# DACs.net
KiCad netlist of a schematic drawn in Altium Designer
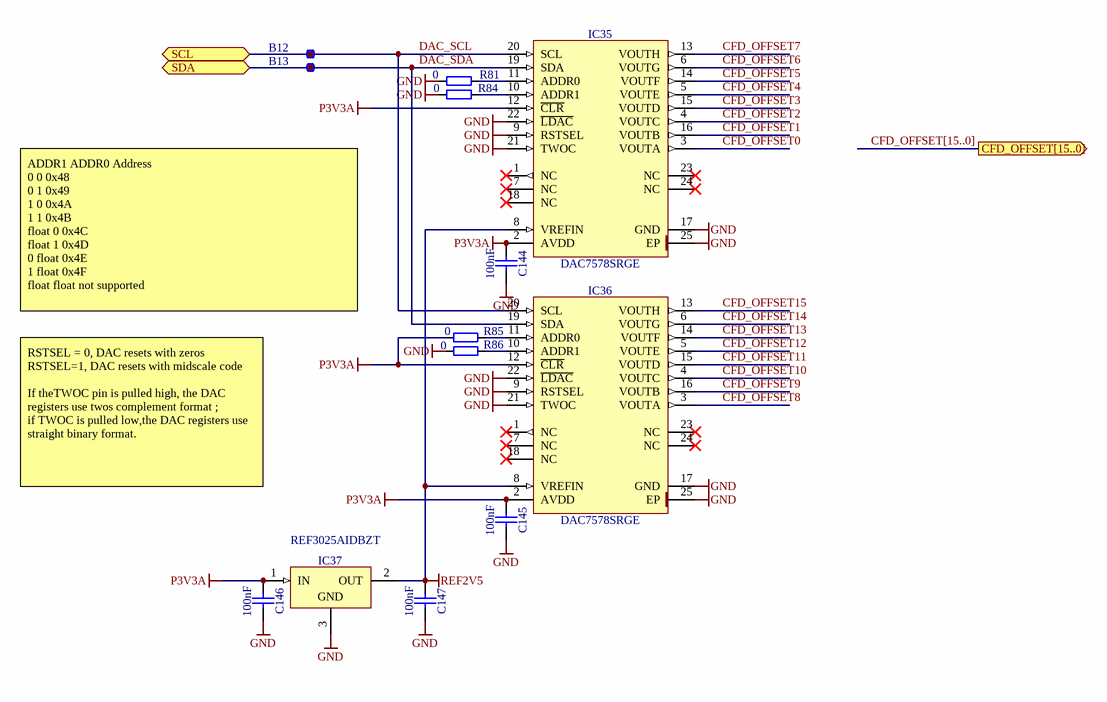
[diagram p0: DACs.SchDoc]

(export (version "E")
  (design (tool "Eeschema 10.0.6"))
  (components
    (comp (ref "B12")
      (value "SMD Pad")
      (footprint "C100")
      (description "Through Hole Pad")
      (fields (field (name "PART NUMBER") "SMD_PAD_D1MM") (field (name "AUTHOR") "CERN DEM JLC"))
      (libsource (lib "Eletro-mechanical") (part "Single SMD Pad (Round)"))
    )
    (comp (ref "B13")
      (value "SMD Pad")
      (footprint "C100")
      (description "Through Hole Pad")
      (fields (field (name "PART NUMBER") "SMD_PAD_D1MM") (field (name "AUTHOR") "CERN DEM JLC"))
      (libsource (lib "Eletro-mechanical") (part "Single SMD Pad (Round)"))
    )
    (comp (ref "C144")
      (value "100nF")
      (footprint "CAPC0603X33N")
      (description "Non-polarised capacitor")
      (fields
        (field (name "PART NUMBER") "CC0201_100NF_6.3V_10%_X5R")
        (field (name "VOLTAGE") "6.3V")
        (field (name "AUTHOR") "CERN DEM JLC")
      )
      (libsource (lib "Capacitors") (part "Capacitor - non polarized"))
    )
    (comp (ref "C145")
      (value "100nF")
      (footprint "CAPC0603X33N")
      (description "Non-polarised capacitor")
      (fields
        (field (name "PART NUMBER") "CC0201_100NF_6.3V_10%_X5R")
        (field (name "VOLTAGE") "6.3V")
        (field (name "AUTHOR") "CERN DEM JLC")
      )
      (libsource (lib "Capacitors") (part "Capacitor - non polarized"))
    )
    (comp (ref "C146")
      (value "100nF")
      (footprint "CAPC0603X33N")
      (description "Non-polarised capacitor")
      (fields
        (field (name "PART NUMBER") "CC0201_100NF_6.3V_10%_X5R")
        (field (name "VOLTAGE") "6.3V")
        (field (name "AUTHOR") "CERN DEM JLC")
      )
      (libsource (lib "Capacitors") (part "Capacitor - non polarized"))
    )
    (comp (ref "C147")
      (value "100nF")
      (footprint "CAPC0603X33N")
      (description "Non-polarised capacitor")
      (fields
        (field (name "PART NUMBER") "CC0201_100NF_6.3V_10%_X5R")
        (field (name "VOLTAGE") "6.3V")
        (field (name "AUTHOR") "CERN DEM JLC")
      )
      (libsource (lib "Capacitors") (part "Capacitor - non polarized"))
    )
    (comp (ref "IC35")
      (value "DAC7578SRGE")
      (footprint "QFN50P400X400X100-25N-S280")
      (fields (field (name "MANUFACTURER") "TEXAS INSTRUMENTS") (field (name "AUTHOR") "CERN DEM MR"))
      (libsource (lib "ICs And Semiconductors") (part "DAC7578SRGE"))
    )
    (comp (ref "IC36")
      (value "DAC7578SRGE")
      (footprint "QFN50P400X400X100-25N-S280")
      (fields (field (name "MANUFACTURER") "TEXAS INSTRUMENTS") (field (name "AUTHOR") "CERN DEM MR"))
      (libsource (lib "ICs And Semiconductors") (part "DAC7578SRGE"))
    )
    (comp (ref "IC37")
      (value "REF3025AIDBZT")
      (footprint "SOT95P237X112-3N")
      (description "3-Terminal Regulator 1=IN 2=OUT 3=GND")
      (fields (field (name "MANUFACTURER") "TEXAS INSTRUMENTS") (field (name "AUTHOR") "CERN DEM JLC"))
      (libsource (lib "ICs And Semiconductors") (part "REG3 1IN-2OUT-3GND"))
    )
    (comp (ref "R81")
      (value "0")
      (footprint "RESC1005X40N")
      (description "Resistor")
      (fields
        (field (name "PART NUMBER") "R0402_0R_JUMPER")
        (field (name "MANUFACTURER") "GENERIC")
        (field (name "AUTHOR") "CERN DEM JLC")
      )
      (libsource (lib "Resistors") (part "Resistor"))
    )
    (comp (ref "R84")
      (value "0")
      (footprint "RESC1005X40N")
      (description "Resistor")
      (fields
        (field (name "PART NUMBER") "R0402_0R_JUMPER")
        (field (name "MANUFACTURER") "GENERIC")
        (field (name "AUTHOR") "CERN DEM JLC")
      )
      (libsource (lib "Resistors") (part "Resistor"))
    )
    (comp (ref "R85")
      (value "0")
      (footprint "RESC1005X40N")
      (description "Resistor")
      (fields
        (field (name "PART NUMBER") "R0402_0R_JUMPER")
        (field (name "MANUFACTURER") "GENERIC")
        (field (name "AUTHOR") "CERN DEM JLC")
      )
      (libsource (lib "Resistors") (part "Resistor"))
    )
    (comp (ref "R86")
      (value "0")
      (footprint "RESC1005X40N")
      (description "Resistor")
      (fields
        (field (name "PART NUMBER") "R0402_0R_JUMPER")
        (field (name "MANUFACTURER") "GENERIC")
        (field (name "AUTHOR") "CERN DEM JLC")
      )
      (libsource (lib "Resistors") (part "Resistor"))
    )
  )
  (nets
    (net (code "1") (name "/CFD_OFFSET0") (class "Default")
      (node (ref "IC35") (pin "3") (pinfunction "VOUTA_3") (pintype "output"))
    )
    (net (code "2") (name "/CFD_OFFSET1") (class "Default")
      (node (ref "IC35") (pin "16") (pinfunction "VOUTB_16") (pintype "output"))
    )
    (net (code "3") (name "/CFD_OFFSET2") (class "Default")
      (node (ref "IC35") (pin "4") (pinfunction "VOUTC_4") (pintype "output"))
    )
    (net (code "4") (name "/CFD_OFFSET3") (class "Default")
      (node (ref "IC35") (pin "15") (pinfunction "VOUTD_15") (pintype "output"))
    )
    (net (code "5") (name "/CFD_OFFSET4") (class "Default")
      (node (ref "IC35") (pin "5") (pinfunction "VOUTE_5") (pintype "output"))
    )
    (net (code "6") (name "/CFD_OFFSET5") (class "Default")
      (node (ref "IC35") (pin "14") (pinfunction "VOUTF_14") (pintype "output"))
    )
    (net (code "7") (name "/CFD_OFFSET6") (class "Default")
      (node (ref "IC35") (pin "6") (pinfunction "VOUTG_6") (pintype "output"))
    )
    (net (code "8") (name "/CFD_OFFSET7") (class "Default")
      (node (ref "IC35") (pin "13") (pinfunction "VOUTH_13") (pintype "output"))
    )
    (net (code "9") (name "/CFD_OFFSET8") (class "Default")
      (node (ref "IC36") (pin "3") (pinfunction "VOUTA_3") (pintype "output"))
    )
    (net (code "10") (name "/CFD_OFFSET9") (class "Default")
      (node (ref "IC36") (pin "16") (pinfunction "VOUTB_16") (pintype "output"))
    )
    (net (code "11") (name "/CFD_OFFSET10") (class "Default")
      (node (ref "IC36") (pin "4") (pinfunction "VOUTC_4") (pintype "output"))
    )
    (net (code "12") (name "/CFD_OFFSET11") (class "Default")
      (node (ref "IC36") (pin "15") (pinfunction "VOUTD_15") (pintype "output"))
    )
    (net (code "13") (name "/CFD_OFFSET12") (class "Default")
      (node (ref "IC36") (pin "5") (pinfunction "VOUTE_5") (pintype "output"))
    )
    (net (code "14") (name "/CFD_OFFSET13") (class "Default")
      (node (ref "IC36") (pin "14") (pinfunction "VOUTF_14") (pintype "output"))
    )
    (net (code "15") (name "/CFD_OFFSET14") (class "Default")
      (node (ref "IC36") (pin "6") (pinfunction "VOUTG_6") (pintype "output"))
    )
    (net (code "16") (name "/CFD_OFFSET15") (class "Default")
      (node (ref "IC36") (pin "13") (pinfunction "VOUTH_13") (pintype "output"))
    )
    (net (code "18") (name "/DAC_SCL") (class "Default")
      (node (ref "B12") (pin "1") (pinfunction "1_1") (pintype "bidirectional"))
      (node (ref "IC35") (pin "20") (pinfunction "SCL_20") (pintype "input"))
      (node (ref "IC36") (pin "20") (pinfunction "SCL_20") (pintype "input"))
    )
    (net (code "19") (name "/DAC_SDA") (class "Default")
      (node (ref "B13") (pin "1") (pinfunction "1_1") (pintype "bidirectional"))
      (node (ref "IC35") (pin "19") (pinfunction "SDA_19") (pintype "input"))
      (node (ref "IC36") (pin "19") (pinfunction "SDA_19") (pintype "input"))
    )
    (net (code "20") (name "GND") (class "Default")
      (node (ref "C144") (pin "2") (pinfunction "2_2") (pintype "passive"))
      (node (ref "C145") (pin "2") (pinfunction "2_2") (pintype "passive"))
      (node (ref "C146") (pin "2") (pinfunction "2_2") (pintype "passive"))
      (node (ref "C147") (pin "2") (pinfunction "2_2") (pintype "passive"))
      (node (ref "IC35") (pin "17") (pinfunction "GND_17") (pintype "power_in"))
      (node (ref "IC35") (pin "21") (pinfunction "TWOC_21") (pintype "input"))
      (node (ref "IC35") (pin "22") (pinfunction "~{LDAC}_22") (pintype "input"))
      (node (ref "IC35") (pin "25") (pinfunction "EP_25") (pintype "power_in"))
      (node (ref "IC35") (pin "9") (pinfunction "RSTSEL_9") (pintype "input"))
      (node (ref "IC36") (pin "17") (pinfunction "GND_17") (pintype "power_in"))
      (node (ref "IC36") (pin "21") (pinfunction "TWOC_21") (pintype "input"))
      (node (ref "IC36") (pin "22") (pinfunction "~{LDAC}_22") (pintype "input"))
      (node (ref "IC36") (pin "25") (pinfunction "EP_25") (pintype "power_in"))
      (node (ref "IC36") (pin "9") (pinfunction "RSTSEL_9") (pintype "input"))
      (node (ref "IC37") (pin "3") (pinfunction "GND_3") (pintype "power_in"))
      (node (ref "R81") (pin "1") (pinfunction "1_1") (pintype "passive"))
      (node (ref "R84") (pin "1") (pinfunction "1_1") (pintype "passive"))
      (node (ref "R86") (pin "1") (pinfunction "1_1") (pintype "passive"))
    )
    (net (code "21") (name "Net-(IC35-ADDR0)") (class "Default")
      (node (ref "IC35") (pin "11") (pinfunction "ADDR0_11") (pintype "input"))
      (node (ref "R81") (pin "2") (pinfunction "2_2") (pintype "passive"))
    )
    (net (code "22") (name "Net-(IC35-ADDR1)") (class "Default")
      (node (ref "IC35") (pin "10") (pinfunction "ADDR1_10") (pintype "input"))
      (node (ref "R84") (pin "2") (pinfunction "2_2") (pintype "passive"))
    )
    (net (code "23") (name "Net-(IC36-ADDR0)") (class "Default")
      (node (ref "IC36") (pin "11") (pinfunction "ADDR0_11") (pintype "input"))
      (node (ref "R85") (pin "2") (pinfunction "2_2") (pintype "passive"))
    )
    (net (code "24") (name "Net-(IC36-ADDR1)") (class "Default")
      (node (ref "IC36") (pin "10") (pinfunction "ADDR1_10") (pintype "input"))
      (node (ref "R86") (pin "2") (pinfunction "2_2") (pintype "passive"))
    )
    (net (code "25") (name "P3V3A") (class "Default")
      (node (ref "C144") (pin "1") (pinfunction "1_1") (pintype "passive"))
      (node (ref "C145") (pin "1") (pinfunction "1_1") (pintype "passive"))
      (node (ref "C146") (pin "1") (pinfunction "1_1") (pintype "passive"))
      (node (ref "IC35") (pin "12") (pinfunction "~{CLR}_12") (pintype "input"))
      (node (ref "IC35") (pin "2") (pinfunction "AVDD_2") (pintype "power_in"))
      (node (ref "IC36") (pin "12") (pinfunction "~{CLR}_12") (pintype "input"))
      (node (ref "IC36") (pin "2") (pinfunction "AVDD_2") (pintype "power_in"))
      (node (ref "IC37") (pin "1") (pinfunction "IN_1") (pintype "input"))
      (node (ref "R85") (pin "1") (pinfunction "1_1") (pintype "passive"))
    )
    (net (code "26") (name "REF2V5") (class "Default")
      (node (ref "C147") (pin "1") (pinfunction "1_1") (pintype "passive"))
      (node (ref "IC35") (pin "8") (pinfunction "VREFIN_8") (pintype "input"))
      (node (ref "IC36") (pin "8") (pinfunction "VREFIN_8") (pintype "input"))
      (node (ref "IC37") (pin "2") (pinfunction "OUT_2") (pintype "power_in"))
    )
    (net (code "27") (name "unconnected-(IC35-NC-Pad1)") (class "Default")
      (node (ref "IC35") (pin "1") (pinfunction "NC_1") (pintype "output+no_connect"))
    )
    (net (code "28") (name "unconnected-(IC35-NC-Pad7)") (class "Default")
      (node (ref "IC35") (pin "7") (pinfunction "NC_7") (pintype "passive+no_connect"))
    )
    (net (code "29") (name "unconnected-(IC35-NC-Pad18)") (class "Default")
      (node (ref "IC35") (pin "18") (pinfunction "NC_18") (pintype "passive+no_connect"))
    )
    (net (code "30") (name "unconnected-(IC35-NC-Pad23)") (class "Default")
      (node (ref "IC35") (pin "23") (pinfunction "NC_23") (pintype "passive+no_connect"))
    )
    (net (code "31") (name "unconnected-(IC35-NC-Pad24)") (class "Default")
      (node (ref "IC35") (pin "24") (pinfunction "NC_24") (pintype "passive+no_connect"))
    )
    (net (code "32") (name "unconnected-(IC36-NC-Pad1)") (class "Default")
      (node (ref "IC36") (pin "1") (pinfunction "NC_1") (pintype "output+no_connect"))
    )
    (net (code "33") (name "unconnected-(IC36-NC-Pad7)") (class "Default")
      (node (ref "IC36") (pin "7") (pinfunction "NC_7") (pintype "passive+no_connect"))
    )
    (net (code "34") (name "unconnected-(IC36-NC-Pad18)") (class "Default")
      (node (ref "IC36") (pin "18") (pinfunction "NC_18") (pintype "passive+no_connect"))
    )
    (net (code "35") (name "unconnected-(IC36-NC-Pad23)") (class "Default")
      (node (ref "IC36") (pin "23") (pinfunction "NC_23") (pintype "passive+no_connect"))
    )
    (net (code "36") (name "unconnected-(IC36-NC-Pad24)") (class "Default")
      (node (ref "IC36") (pin "24") (pinfunction "NC_24") (pintype "passive+no_connect"))
    )
  )
)
